# mcu.net
KiCad netlist of a schematic drawn in Altium Designer
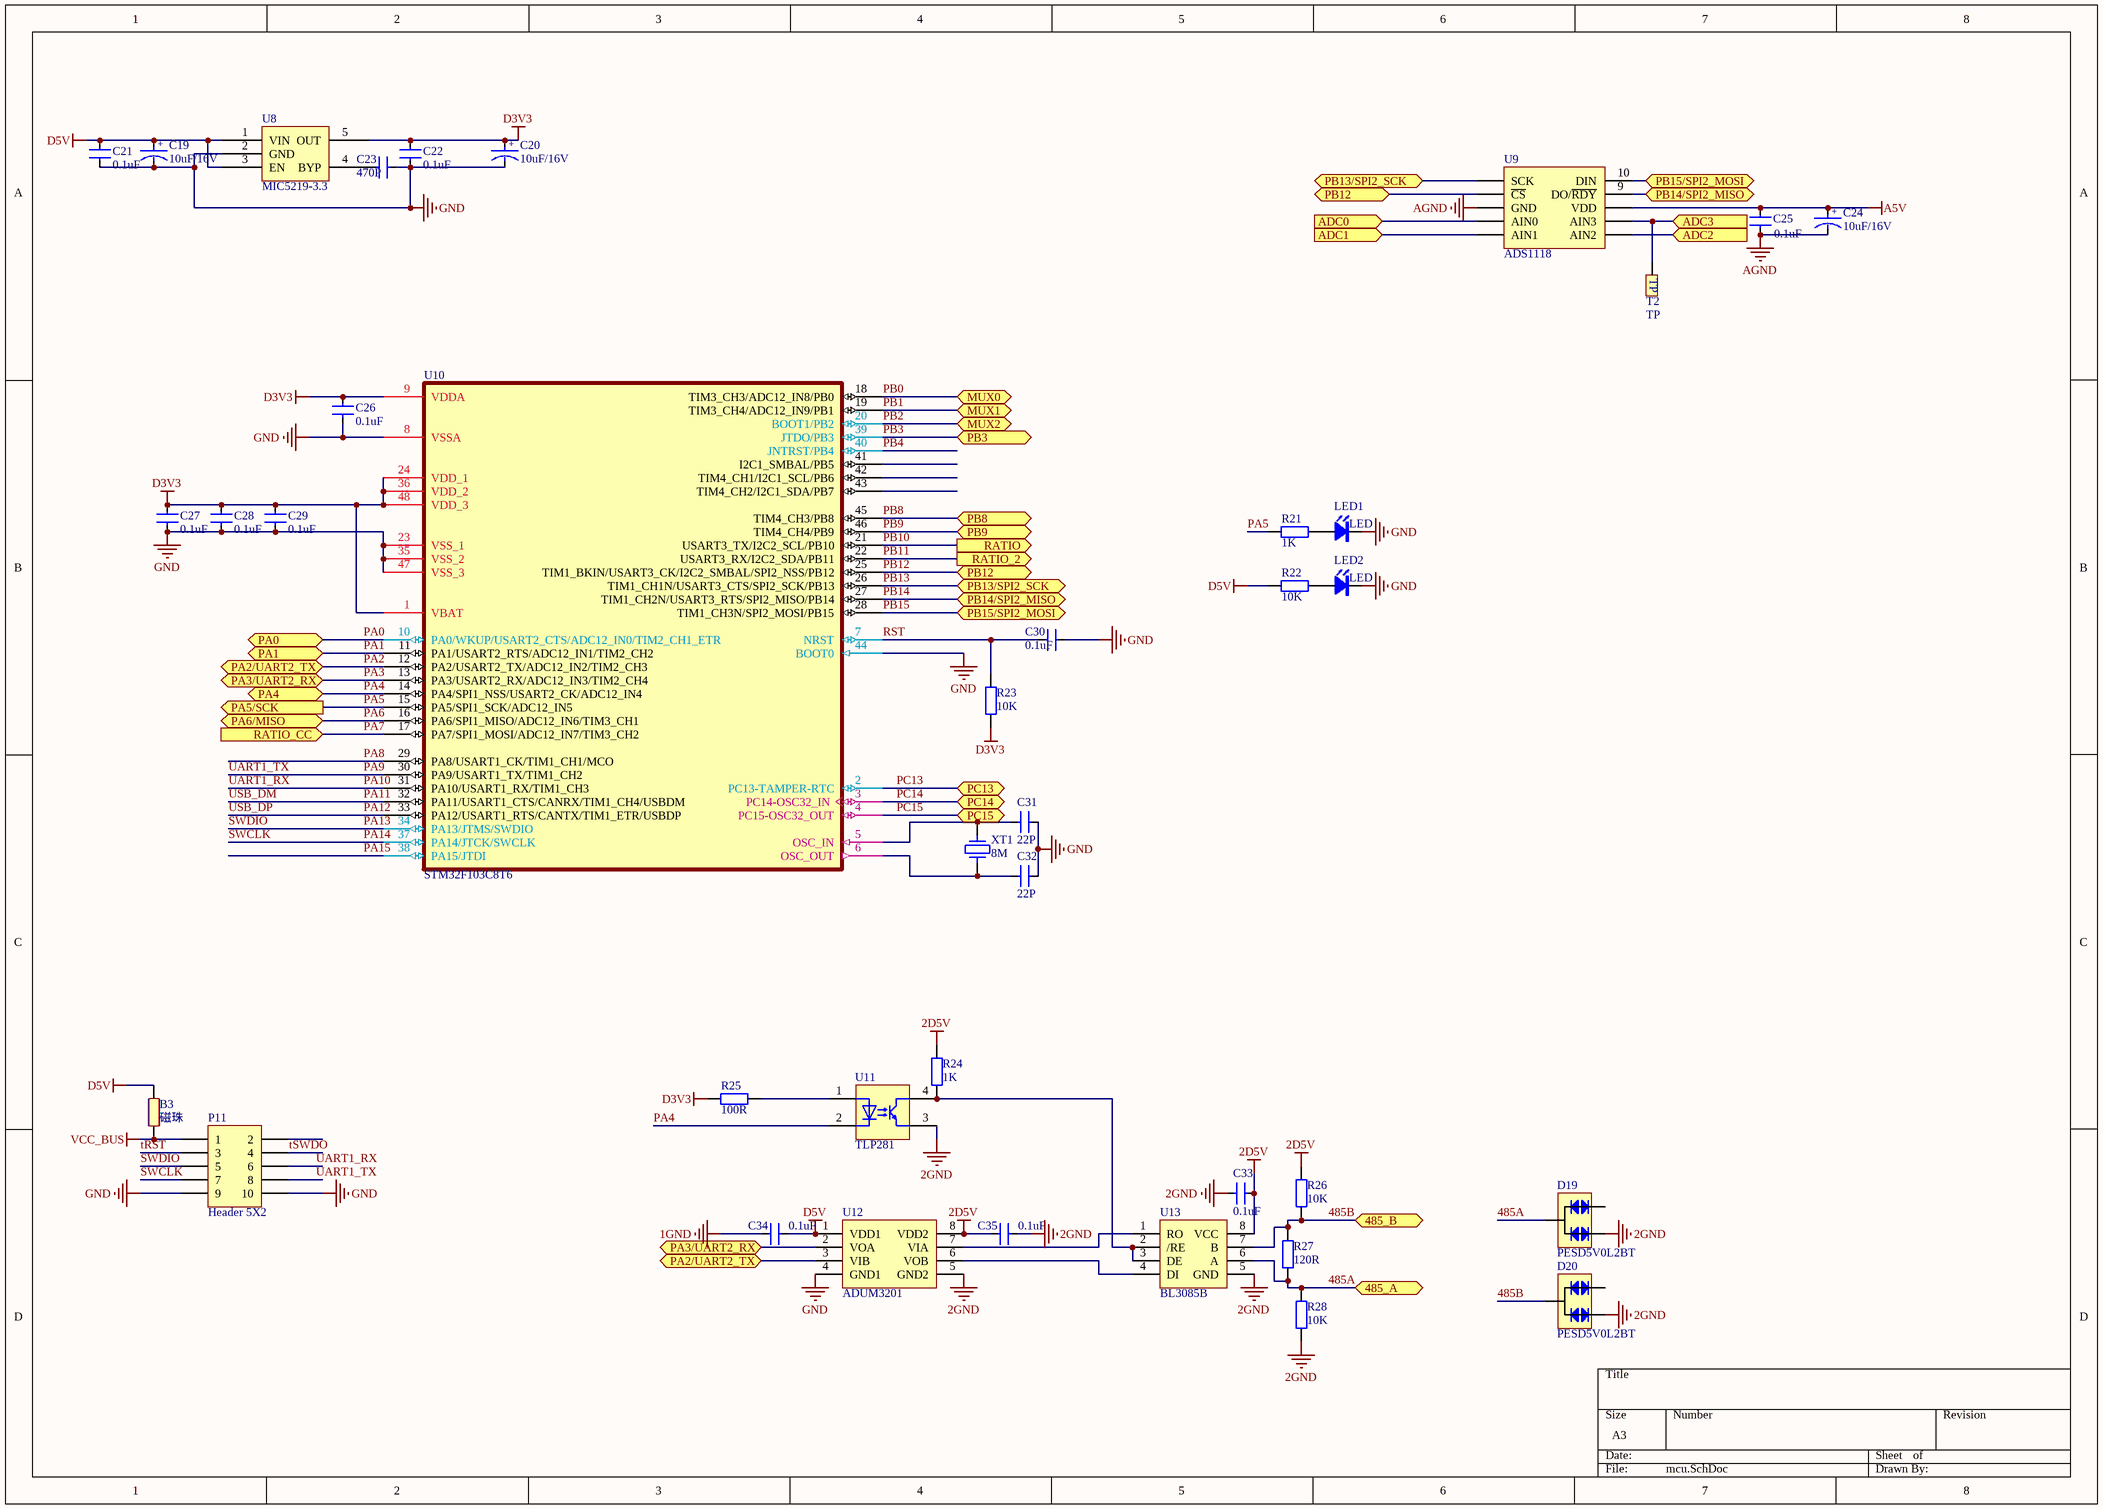
[diagram p0: mcu.SchDoc]

(export (version "E")
  (design (tool "Eeschema 10.0.6"))
  (components
    (comp (ref "B3") (value "磁珠") (footprint "0603L") (libsource (lib "lib_AD") (part "BEAD")))
    (comp (ref "C19")
      (value "10uF/16V")
      (footprint "3216C")
      (description "钽电容")
      (libsource (lib "lib_AD") (part "CAP-T"))
    )
    (comp (ref "C20")
      (value "10uF/16V")
      (footprint "3216C")
      (description "钽电容")
      (libsource (lib "lib_AD") (part "CAP-T"))
    )
    (comp (ref "C21")
      (value "0.1uF")
      (footprint "0603C")
      (description "普通小电容")
      (libsource (lib "lib_AD") (part "CAP"))
    )
    (comp (ref "C22")
      (value "0.1uF")
      (footprint "0603C")
      (description "普通小电容")
      (libsource (lib "lib_AD") (part "CAP"))
    )
    (comp (ref "C23")
      (value "470P")
      (footprint "0603C")
      (description "普通小电容")
      (libsource (lib "lib_GMDZ") (part "CAP"))
    )
    (comp (ref "C24")
      (value "10uF/16V")
      (footprint "3216C")
      (description "钽电容")
      (libsource (lib "lib_AD") (part "CAP-T"))
    )
    (comp (ref "C25")
      (value "0.1uF")
      (footprint "0603C")
      (description "普通小电容")
      (libsource (lib "lib_AD") (part "CAP"))
    )
    (comp (ref "C26")
      (value "0.1uF")
      (footprint "0603C")
      (description "普通小电容")
      (libsource (lib "lib_GMDZ") (part "CAP"))
    )
    (comp (ref "C27")
      (value "0.1uF")
      (footprint "0603C")
      (description "普通小电容")
      (libsource (lib "lib_GMDZ") (part "CAP"))
    )
    (comp (ref "C28")
      (value "0.1uF")
      (footprint "0603C")
      (description "普通小电容")
      (libsource (lib "lib_GMDZ") (part "CAP"))
    )
    (comp (ref "C29")
      (value "0.1uF")
      (footprint "0603C")
      (description "普通小电容")
      (libsource (lib "lib_GMDZ") (part "CAP"))
    )
    (comp (ref "C30")
      (value "0.1uF")
      (footprint "0603C")
      (description "普通小电容")
      (libsource (lib "") (part "CAP_1"))
    )
    (comp (ref "C31")
      (value "22P")
      (footprint "0603C")
      (description "普通小电容")
      (libsource (lib "") (part "CAP_1"))
    )
    (comp (ref "C32")
      (value "22P")
      (footprint "0603C")
      (description "普通小电容")
      (libsource (lib "") (part "CAP_1"))
    )
    (comp (ref "C33")
      (value "0.1uF")
      (footprint "0603C")
      (description "普通小电容")
      (libsource (lib "") (part "CAP_1"))
    )
    (comp (ref "C34")
      (value "0.1uF")
      (footprint "0603C")
      (description "普通小电容")
      (libsource (lib "") (part "CAP_1"))
    )
    (comp (ref "C35")
      (value "0.1uF")
      (footprint "0603C")
      (description "普通小电容")
      (libsource (lib "") (part "CAP_1"))
    )
    (comp (ref "D19")
      (value "PESD5V0L2BT")
      (footprint "SOT23A")
      (description "schottky diod")
      (libsource (lib "R_C_L_D") (part "PESD5V0L2BT"))
    )
    (comp (ref "D20")
      (value "PESD5V0L2BT")
      (footprint "SOT23A")
      (description "schottky diod")
      (libsource (lib "R_C_L_D") (part "PESD5V0L2BT"))
    )
    (comp (ref "LED1") (value "LED") (footprint "LED-3") (libsource (lib "lib_AD") (part "LED")))
    (comp (ref "LED2") (value "LED") (footprint "LED-3") (libsource (lib "lib_AD") (part "LED")))
    (comp (ref "P11")
      (value "Header 5X2")
      (footprint "DC2.54-10")
      (description "Header, 5-Pin, Dual row")
      (fields (field (name "PUBLISHER") "Altium Limited"))
      (libsource (lib "Header") (part "Header 5X2"))
    )
    (comp (ref "R21")
      (value "1K")
      (footprint "0603R")
      (description "普通电阻")
      (libsource (lib "") (part "RES_1"))
    )
    (comp (ref "R22")
      (value "10K")
      (footprint "0603R")
      (description "普通电阻")
      (libsource (lib "") (part "RES_1"))
    )
    (comp (ref "R23")
      (value "10K")
      (footprint "0603R")
      (description "普通电阻")
      (libsource (lib "lib_AD") (part "RES"))
    )
    (comp (ref "R24")
      (value "1K")
      (footprint "0603R")
      (description "普通电阻")
      (libsource (lib "lib_AD") (part "RES"))
    )
    (comp (ref "R25")
      (value "100R")
      (footprint "0603R")
      (description "普通电阻")
      (libsource (lib "") (part "RES_2"))
    )
    (comp (ref "R26")
      (value "10K")
      (footprint "0603R")
      (description "普通电阻")
      (libsource (lib "lib_AD") (part "RES"))
    )
    (comp (ref "R27")
      (value "120R")
      (footprint "0603R")
      (description "普通电阻")
      (libsource (lib "lib_AD") (part "RES"))
    )
    (comp (ref "R28")
      (value "10K")
      (footprint "0603R")
      (description "普通电阻")
      (libsource (lib "lib_AD") (part "RES"))
    )
    (comp (ref "T2")
      (value "TP")
      (footprint "TESTP")
      (description "testpoint")
      (libsource (lib "lib_AD") (part "TP"))
    )
    (comp (ref "U8")
      (value "MIC5219-3.3")
      (footprint "SOT23-5")
      (libsource (lib "lib_GMDZ") (part "MIC5219"))
    )
    (comp (ref "U9")
      (value "ADS1118")
      (footprint "TSSOP10")
      (description "16位 ADC")
      (libsource (lib "lib_AD") (part "ADS1118"))
    )
    (comp (ref "U10")
      (value "STM32F103C8T6")
      (footprint "LQFP48")
      (libsource (lib "lib_GMDZ") (part "STM32F103"))
    )
    (comp (ref "U11")
      (value "TLP281")
      (footprint "SOP4")
      (description "TLP281 光耦")
      (libsource (lib "lib_AD") (part "TLP281"))
    )
    (comp (ref "U12") (value "ADUM3201") (footprint "SOP8") (libsource (lib "lib_AD") (part "ADUM3201")))
    (comp (ref "U13")
      (value "BL3085B")
      (footprint "SOP8")
      (description "BL3085B 15KV防静电485")
      (libsource (lib "lib_AD") (part "BL3085B"))
    )
    (comp (ref "XT1")
      (value "8M")
      (footprint "5032")
      (description "晶振")
      (libsource (lib "lib_GMDZ") (part "XT"))
    )
  )
  (nets
    (net (code "1") (name "/485A") (class "Default")
      (node (ref "D19") (pin "3") (pinfunction "3_3") (pintype "passive"))
      (node (ref "R27") (pin "1") (pinfunction "1_1") (pintype "passive"))
      (node (ref "R28") (pin "2") (pinfunction "2_2") (pintype "passive"))
      (node (ref "U13") (pin "6") (pinfunction "A_6") (pintype "passive"))
    )
    (net (code "2") (name "/485B") (class "Default")
      (node (ref "D20") (pin "3") (pinfunction "3_3") (pintype "passive"))
      (node (ref "R26") (pin "1") (pinfunction "1_1") (pintype "passive"))
      (node (ref "R27") (pin "2") (pinfunction "2_2") (pintype "passive"))
      (node (ref "U13") (pin "7") (pinfunction "B_7") (pintype "passive"))
    )
    (net (code "3") (name "/ADC0") (class "Default")
      (node (ref "U9") (pin "4") (pinfunction "AIN0_4") (pintype "passive"))
    )
    (net (code "4") (name "/ADC1") (class "Default")
      (node (ref "U9") (pin "5") (pinfunction "AIN1_5") (pintype "passive"))
    )
    (net (code "5") (name "/ADC2") (class "Default")
      (node (ref "U9") (pin "6") (pinfunction "AIN2_6") (pintype "passive"))
    )
    (net (code "6") (name "/ADC3") (class "Default")
      (node (ref "T2") (pin "1") (pinfunction "1_1") (pintype "passive"))
      (node (ref "U9") (pin "7") (pinfunction "AIN3_7") (pintype "passive"))
    )
    (net (code "10") (name "/PA0") (class "Default")
      (node (ref "U10") (pin "10") (pinfunction "PA0/WKUP/USART2_CTS/ADC12_IN0/TIM2_CH1_ETR_10") (pintype "bidirectional"))
    )
    (net (code "11") (name "/PA1") (class "Default")
      (node (ref "U10") (pin "11") (pinfunction "PA1/USART2_RTS/ADC12_IN1/TIM2_CH2_11") (pintype "bidirectional"))
    )
    (net (code "12") (name "/PA2") (class "Default")
      (node (ref "U10") (pin "12") (pinfunction "PA2/USART2_TX/ADC12_IN2/TIM2_CH3_12") (pintype "bidirectional"))
      (node (ref "U12") (pin "3") (pinfunction "VIB_3") (pintype "passive"))
    )
    (net (code "13") (name "/PA3") (class "Default")
      (node (ref "U10") (pin "13") (pinfunction "PA3/USART2_RX/ADC12_IN3/TIM2_CH4_13") (pintype "bidirectional"))
      (node (ref "U12") (pin "2") (pinfunction "VOA_2") (pintype "passive"))
    )
    (net (code "14") (name "/PA4") (class "Default")
      (node (ref "U10") (pin "14") (pinfunction "PA4/SPI1_NSS/USART2_CK/ADC12_IN4_14") (pintype "bidirectional"))
      (node (ref "U11") (pin "2") (pinfunction "2_2") (pintype "passive"))
    )
    (net (code "15") (name "/PA5") (class "Default")
      (node (ref "R21") (pin "1") (pinfunction "1_1") (pintype "passive"))
      (node (ref "U10") (pin "15") (pinfunction "PA5/SPI1_SCK/ADC12_IN5_15") (pintype "bidirectional"))
    )
    (net (code "16") (name "/PA6") (class "Default")
      (node (ref "U10") (pin "16") (pinfunction "PA6/SPI1_MISO/ADC12_IN6/TIM3_CH1_16") (pintype "bidirectional"))
    )
    (net (code "17") (name "/PA7") (class "Default")
      (node (ref "U10") (pin "17") (pinfunction "PA7/SPI1_MOSI/ADC12_IN7/TIM3_CH2_17") (pintype "bidirectional"))
    )
    (net (code "18") (name "/PA8") (class "Default")
      (node (ref "U10") (pin "29") (pinfunction "PA8/USART1_CK/TIM1_CH1/MCO_29") (pintype "bidirectional"))
    )
    (net (code "19") (name "/PA9") (class "Default")
      (node (ref "P11") (pin "8") (pinfunction "8_8") (pintype "passive"))
      (node (ref "U10") (pin "30") (pinfunction "PA9/USART1_TX/TIM1_CH2_30") (pintype "bidirectional"))
    )
    (net (code "20") (name "/PA10") (class "Default")
      (node (ref "P11") (pin "6") (pinfunction "6_6") (pintype "passive"))
      (node (ref "U10") (pin "31") (pinfunction "PA10/USART1_RX/TIM1_CH3_31") (pintype "bidirectional"))
    )
    (net (code "21") (name "/PA11") (class "Default")
      (node (ref "U10") (pin "32") (pinfunction "PA11/USART1_CTS/CANRX/TIM1_CH4/USBDM_32") (pintype "bidirectional"))
    )
    (net (code "22") (name "/PA12") (class "Default")
      (node (ref "U10") (pin "33") (pinfunction "PA12/USART1_RTS/CANTX/TIM1_ETR/USBDP_33") (pintype "bidirectional"))
    )
    (net (code "23") (name "/PA13") (class "Default")
      (node (ref "P11") (pin "5") (pinfunction "5_5") (pintype "passive"))
      (node (ref "U10") (pin "34") (pinfunction "PA13/JTMS/SWDIO_34") (pintype "bidirectional"))
    )
    (net (code "24") (name "/PA14") (class "Default")
      (node (ref "P11") (pin "7") (pinfunction "7_7") (pintype "passive"))
      (node (ref "U10") (pin "37") (pinfunction "PA14/JTCK/SWCLK_37") (pintype "bidirectional"))
    )
    (net (code "25") (name "/PA15") (class "Default")
      (node (ref "U10") (pin "38") (pinfunction "PA15/JTDI_38") (pintype "bidirectional"))
    )
    (net (code "26") (name "/PB0") (class "Default")
      (node (ref "U10") (pin "18") (pinfunction "TIM3_CH3/ADC12_IN8/PB0_18") (pintype "bidirectional"))
    )
    (net (code "27") (name "/PB1") (class "Default")
      (node (ref "U10") (pin "19") (pinfunction "TIM3_CH4/ADC12_IN9/PB1_19") (pintype "bidirectional"))
    )
    (net (code "28") (name "/PB2") (class "Default")
      (node (ref "U10") (pin "20") (pinfunction "BOOT1/PB2_20") (pintype "bidirectional"))
    )
    (net (code "29") (name "/PB3") (class "Default")
      (node (ref "U10") (pin "39") (pinfunction "JTDO/PB3_39") (pintype "bidirectional"))
    )
    (net (code "30") (name "/PB4") (class "Default")
      (node (ref "U10") (pin "40") (pinfunction "JNTRST/PB4_40") (pintype "bidirectional"))
    )
    (net (code "31") (name "/PB8") (class "Default")
      (node (ref "U10") (pin "45") (pinfunction "TIM4_CH3/PB8_45") (pintype "bidirectional"))
    )
    (net (code "32") (name "/PB9") (class "Default")
      (node (ref "U10") (pin "46") (pinfunction "TIM4_CH4/PB9_46") (pintype "bidirectional"))
    )
    (net (code "33") (name "/PB10") (class "Default")
      (node (ref "U10") (pin "21") (pinfunction "USART3_TX/I2C2_SCL/PB10_21") (pintype "bidirectional"))
    )
    (net (code "34") (name "/PB11") (class "Default")
      (node (ref "U10") (pin "22") (pinfunction "USART3_RX/I2C2_SDA/PB11_22") (pintype "bidirectional"))
    )
    (net (code "35") (name "/PB12") (class "Default")
      (node (ref "U10") (pin "25") (pinfunction "TIM1_BKIN/USART3_CK/I2C2_SMBAL/SPI2_NSS/PB12_25") (pintype "bidirectional"))
      (node (ref "U9") (pin "2") (pinfunction "~{CS}_2") (pintype "passive"))
    )
    (net (code "36") (name "/PB13") (class "Default")
      (node (ref "U10") (pin "26") (pinfunction "TIM1_CH1N/USART3_CTS/SPI2_SCK/PB13_26") (pintype "bidirectional"))
      (node (ref "U9") (pin "1") (pinfunction "SCK_1") (pintype "passive"))
    )
    (net (code "37") (name "/PB14") (class "Default")
      (node (ref "U10") (pin "27") (pinfunction "TIM1_CH2N/USART3_RTS/SPI2_MISO/PB14_27") (pintype "bidirectional"))
      (node (ref "U9") (pin "9") (pinfunction "DO/~{RDY}_9") (pintype "passive"))
    )
    (net (code "38") (name "/PB15") (class "Default")
      (node (ref "U10") (pin "28") (pinfunction "TIM1_CH3N/SPI2_MOSI/PB15_28") (pintype "bidirectional"))
      (node (ref "U9") (pin "10") (pinfunction "DIN_10") (pintype "passive"))
    )
    (net (code "39") (name "/PC13") (class "Default")
      (node (ref "U10") (pin "2") (pinfunction "PC13-TAMPER-RTC_2") (pintype "bidirectional"))
    )
    (net (code "40") (name "/PC14") (class "Default")
      (node (ref "U10") (pin "3") (pinfunction "PC14-OSC32_IN_3") (pintype "bidirectional"))
    )
    (net (code "41") (name "/PC15") (class "Default")
      (node (ref "U10") (pin "4") (pinfunction "PC15-OSC32_OUT_4") (pintype "bidirectional"))
    )
    (net (code "42") (name "/RST") (class "Default")
      (node (ref "C30") (pin "1") (pinfunction "1_1") (pintype "passive"))
      (node (ref "R23") (pin "2") (pinfunction "2_2") (pintype "passive"))
      (node (ref "U10") (pin "7") (pinfunction "NRST_7") (pintype "bidirectional"))
    )
    (net (code "43") (name "/tRST") (class "Default")
      (node (ref "P11") (pin "3") (pinfunction "3_3") (pintype "passive"))
    )
    (net (code "44") (name "/tSWDO") (class "Default")
      (node (ref "P11") (pin "4") (pinfunction "4_4") (pintype "passive"))
    )
    (net (code "45") (name "1GND") (class "Default")
      (node (ref "C34") (pin "2") (pinfunction "2_2") (pintype "passive"))
    )
    (net (code "46") (name "2D5V") (class "Default")
      (node (ref "C33") (pin "2") (pinfunction "2_2") (pintype "passive"))
      (node (ref "C35") (pin "2") (pinfunction "2_2") (pintype "passive"))
      (node (ref "R24") (pin "2") (pinfunction "2_2") (pintype "passive"))
      (node (ref "R26") (pin "2") (pinfunction "2_2") (pintype "passive"))
      (node (ref "U12") (pin "8") (pinfunction "VDD2_8") (pintype "passive"))
      (node (ref "U13") (pin "8") (pinfunction "VCC_8") (pintype "passive"))
    )
    (net (code "47") (name "2GND") (class "Default")
      (node (ref "C33") (pin "1") (pinfunction "1_1") (pintype "passive"))
      (node (ref "C35") (pin "1") (pinfunction "1_1") (pintype "passive"))
      (node (ref "D19") (pin "1") (pinfunction "1_1") (pintype "passive"))
      (node (ref "D20") (pin "1") (pinfunction "1_1") (pintype "passive"))
      (node (ref "R28") (pin "1") (pinfunction "1_1") (pintype "passive"))
      (node (ref "U11") (pin "3") (pinfunction "3_3") (pintype "passive"))
      (node (ref "U12") (pin "5") (pinfunction "GND2_5") (pintype "passive"))
      (node (ref "U13") (pin "5") (pinfunction "GND_5") (pintype "passive"))
    )
    (net (code "48") (name "A5V") (class "Default")
      (node (ref "C24") (pin "1") (pinfunction "1_1") (pintype "passive"))
      (node (ref "C25") (pin "2") (pinfunction "2_2") (pintype "passive"))
      (node (ref "U9") (pin "8") (pinfunction "VDD_8") (pintype "passive"))
    )
    (net (code "49") (name "AGND") (class "Default")
      (node (ref "C24") (pin "2") (pinfunction "2_2") (pintype "passive"))
      (node (ref "C25") (pin "1") (pinfunction "1_1") (pintype "passive"))
      (node (ref "U9") (pin "3") (pinfunction "GND_3") (pintype "passive"))
    )
    (net (code "50") (name "D3V3") (class "Default")
      (node (ref "C20") (pin "1") (pinfunction "1_1") (pintype "passive"))
      (node (ref "C22") (pin "2") (pinfunction "2_2") (pintype "passive"))
      (node (ref "C26") (pin "2") (pinfunction "2_2") (pintype "passive"))
      (node (ref "C27") (pin "2") (pinfunction "2_2") (pintype "passive"))
      (node (ref "C28") (pin "1") (pinfunction "1_1") (pintype "passive"))
      (node (ref "C29") (pin "2") (pinfunction "2_2") (pintype "passive"))
      (node (ref "R23") (pin "1") (pinfunction "1_1") (pintype "passive"))
      (node (ref "R25") (pin "2") (pinfunction "2_2") (pintype "passive"))
      (node (ref "U10") (pin "1") (pinfunction "VBAT_1") (pintype "power_in"))
      (node (ref "U10") (pin "24") (pinfunction "VDD_1_24") (pintype "power_in"))
      (node (ref "U10") (pin "36") (pinfunction "VDD_2_36") (pintype "power_in"))
      (node (ref "U10") (pin "48") (pinfunction "VDD_3_48") (pintype "power_in"))
      (node (ref "U10") (pin "9") (pinfunction "VDDA_9") (pintype "power_in"))
      (node (ref "U8") (pin "5") (pinfunction "OUT_5") (pintype "passive"))
    )
    (net (code "51") (name "D5V") (class "Default")
      (node (ref "B3") (pin "2") (pinfunction "2_2") (pintype "passive"))
      (node (ref "C19") (pin "1") (pinfunction "1_1") (pintype "passive"))
      (node (ref "C21") (pin "2") (pinfunction "2_2") (pintype "passive"))
      (node (ref "C34") (pin "1") (pinfunction "1_1") (pintype "passive"))
      (node (ref "R22") (pin "1") (pinfunction "1_1") (pintype "passive"))
      (node (ref "U12") (pin "1") (pinfunction "VDD1_1") (pintype "passive"))
      (node (ref "U8") (pin "1") (pinfunction "VIN_1") (pintype "passive"))
      (node (ref "U8") (pin "3") (pinfunction "EN_3") (pintype "passive"))
    )
    (net (code "52") (name "GND") (class "Default")
      (node (ref "C19") (pin "2") (pinfunction "2_2") (pintype "passive"))
      (node (ref "C20") (pin "2") (pinfunction "2_2") (pintype "passive"))
      (node (ref "C21") (pin "1") (pinfunction "1_1") (pintype "passive"))
      (node (ref "C22") (pin "1") (pinfunction "1_1") (pintype "passive"))
      (node (ref "C23") (pin "2") (pinfunction "2_2") (pintype "passive"))
      (node (ref "C26") (pin "1") (pinfunction "1_1") (pintype "passive"))
      (node (ref "C27") (pin "1") (pinfunction "1_1") (pintype "passive"))
      (node (ref "C28") (pin "2") (pinfunction "2_2") (pintype "passive"))
      (node (ref "C29") (pin "1") (pinfunction "1_1") (pintype "passive"))
      (node (ref "C30") (pin "2") (pinfunction "2_2") (pintype "passive"))
      (node (ref "C31") (pin "2") (pinfunction "2_2") (pintype "passive"))
      (node (ref "C32") (pin "2") (pinfunction "2_2") (pintype "passive"))
      (node (ref "LED1") (pin "K") (pinfunction "2_K") (pintype "passive"))
      (node (ref "LED2") (pin "K") (pinfunction "2_K") (pintype "passive"))
      (node (ref "P11") (pin "10") (pinfunction "10_10") (pintype "passive"))
      (node (ref "P11") (pin "9") (pinfunction "9_9") (pintype "passive"))
      (node (ref "U10") (pin "23") (pinfunction "VSS_1_23") (pintype "power_in"))
      (node (ref "U10") (pin "35") (pinfunction "VSS_2_35") (pintype "power_in"))
      (node (ref "U10") (pin "44") (pinfunction "BOOT0_44") (pintype "input"))
      (node (ref "U10") (pin "47") (pinfunction "VSS_3_47") (pintype "power_in"))
      (node (ref "U10") (pin "8") (pinfunction "VSSA_8") (pintype "power_in"))
      (node (ref "U12") (pin "4") (pinfunction "GND1_4") (pintype "passive"))
      (node (ref "U8") (pin "2") (pinfunction "GND_2") (pintype "passive"))
    )
    (net (code "53") (name "Net-(LED1-1)") (class "Default")
      (node (ref "LED1") (pin "A") (pinfunction "1_A") (pintype "passive"))
      (node (ref "R21") (pin "2") (pinfunction "2_2") (pintype "passive"))
    )
    (net (code "54") (name "Net-(LED2-1)") (class "Default")
      (node (ref "LED2") (pin "A") (pinfunction "1_A") (pintype "passive"))
      (node (ref "R22") (pin "2") (pinfunction "2_2") (pintype "passive"))
    )
    (net (code "55") (name "Net-(R25-Pad1)") (class "Default")
      (node (ref "R25") (pin "1") (pinfunction "1_1") (pintype "passive"))
      (node (ref "U11") (pin "1") (pinfunction "1_1") (pintype "passive"))
    )
    (net (code "56") (name "Net-(U8-BYP)") (class "Default")
      (node (ref "C23") (pin "1") (pinfunction "1_1") (pintype "passive"))
      (node (ref "U8") (pin "4") (pinfunction "BYP_4") (pintype "passive"))
    )
    (net (code "57") (name "Net-(U10-OSC_IN)") (class "Default")
      (node (ref "C31") (pin "1") (pinfunction "1_1") (pintype "passive"))
      (node (ref "U10") (pin "5") (pinfunction "OSC_IN_5") (pintype "input"))
      (node (ref "XT1") (pin "1") (pinfunction "1_1") (pintype "passive"))
    )
    (net (code "58") (name "Net-(U10-OSC_OUT)") (class "Default")
      (node (ref "C32") (pin "1") (pinfunction "1_1") (pintype "passive"))
      (node (ref "U10") (pin "6") (pinfunction "OSC_OUT_6") (pintype "output"))
      (node (ref "XT1") (pin "2") (pinfunction "2_2") (pintype "passive"))
    )
    (net (code "59") (name "Net-(U12-VIA)") (class "Default")
      (node (ref "U12") (pin "7") (pinfunction "VIA_7") (pintype "passive"))
      (node (ref "U13") (pin "1") (pinfunction "RO_1") (pintype "passive"))
    )
    (net (code "60") (name "Net-(U12-VOB)") (class "Default")
      (node (ref "U12") (pin "6") (pinfunction "VOB_6") (pintype "passive"))
      (node (ref "U13") (pin "4") (pinfunction "DI_4") (pintype "passive"))
    )
    (net (code "61") (name "Net-(U13-DE)") (class "Default")
      (node (ref "R24") (pin "1") (pinfunction "1_1") (pintype "passive"))
      (node (ref "U11") (pin "4") (pinfunction "4_4") (pintype "passive"))
      (node (ref "U13") (pin "2") (pinfunction "/RE_2") (pintype "passive"))
      (node (ref "U13") (pin "3") (pinfunction "DE_3") (pintype "passive"))
    )
    (net (code "62") (name "VCC_BUS") (class "Default")
      (node (ref "B3") (pin "1") (pinfunction "1_1") (pintype "passive"))
      (node (ref "P11") (pin "1") (pinfunction "1_1") (pintype "passive"))
    )
    (net (code "63") (name "unconnected-(D19-Pad2)") (class "Default")
      (node (ref "D19") (pin "2") (pinfunction "2_2") (pintype "passive"))
    )
    (net (code "64") (name "unconnected-(D20-Pad2)") (class "Default")
      (node (ref "D20") (pin "2") (pinfunction "2_2") (pintype "passive"))
    )
    (net (code "65") (name "unconnected-(P11-Pad2)") (class "Default")
      (node (ref "P11") (pin "2") (pinfunction "2_2") (pintype "passive"))
    )
    (net (code "66") (name "unconnected-(U10-I2C1_SMBAL{slash}PB5-Pad41)") (class "Default")
      (node (ref "U10") (pin "41") (pinfunction "I2C1_SMBAL/PB5_41") (pintype "bidirectional"))
    )
    (net (code "67") (name "unconnected-(U10-TIM4_CH1{slash}I2C1_SCL{slash}PB6-Pad42)") (class "Default")
      (node (ref "U10") (pin "42") (pinfunction "TIM4_CH1/I2C1_SCL/PB6_42") (pintype "bidirectional"))
    )
    (net (code "68") (name "unconnected-(U10-TIM4_CH2{slash}I2C1_SDA{slash}PB7-Pad43)") (class "Default")
      (node (ref "U10") (pin "43") (pinfunction "TIM4_CH2/I2C1_SDA/PB7_43") (pintype "bidirectional"))
    )
  )
)
